# zehnder-comfoair-esp32.net
KiCad netlist of a schematic drawn in Altium Designer
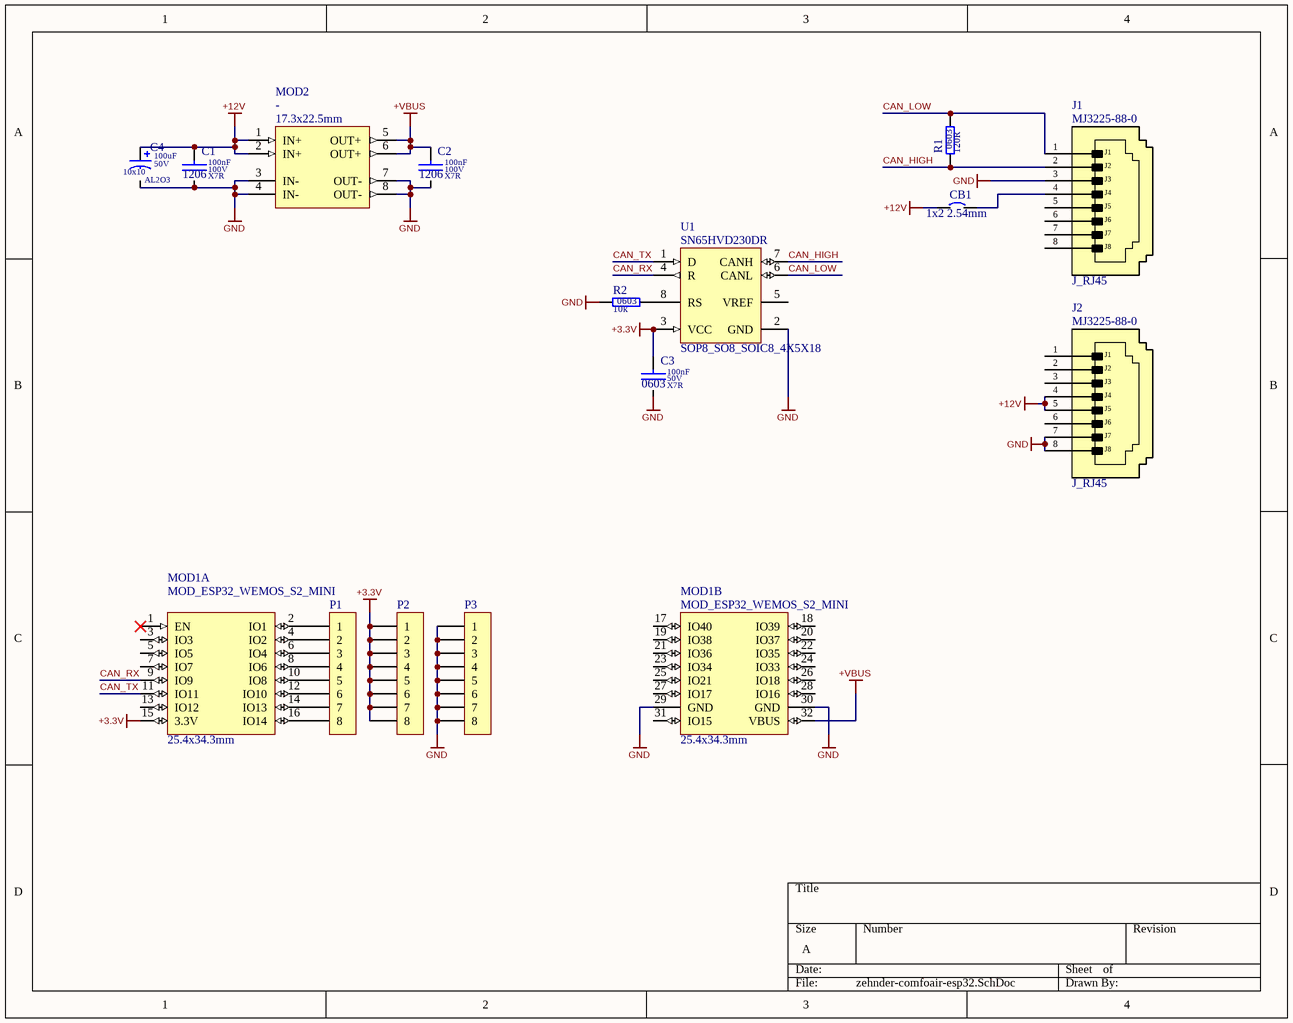
[diagram p0: zehnder-comfoair-esp32.SchDoc]

(export (version "E")
  (design (tool "Eeschema 10.0.6"))
  (components
    (comp (ref "C1")
      (value "100nF")
      (footprint "C_1206_3216")
      (description "Capacitor")
      (fields
        (field (name "DIELECTRIC") "X7R")
        (field (name "VOLTAGE") "100V")
        (field (name "SCH_FOOTPRINT") "1206")
        (field (name "PART NUMBER") "C_100nF_100V_X7R_1206_10")
        (field (name "MANUFACTURER") "Samsung")
      )
      (libsource (lib "Library") (part "C"))
    )
    (comp (ref "C2")
      (value "100nF")
      (footprint "C_1206_3216")
      (description "Capacitor")
      (fields
        (field (name "DIELECTRIC") "X7R")
        (field (name "VOLTAGE") "100V")
        (field (name "SCH_FOOTPRINT") "1206")
        (field (name "PART NUMBER") "C_100nF_100V_X7R_1206_10")
        (field (name "MANUFACTURER") "Samsung")
      )
      (libsource (lib "Library") (part "C"))
    )
    (comp (ref "C3")
      (value "100nF")
      (footprint "C_0603_1608")
      (description "Capacitor")
      (fields
        (field (name "DIELECTRIC") "X7R")
        (field (name "VOLTAGE") "50V")
        (field (name "SCH_FOOTPRINT") "0603")
        (field (name "PART NUMBER") "C_100nF_50V_X7R_0603_5")
        (field (name "MANUFACTURER") "Samsung")
      )
      (libsource (lib "Library") (part "C"))
    )
    (comp (ref "C4")
      (value "100uF")
      (footprint "CE_D_10x10MM")
      (description "Polarized Capacitor")
      (fields
        (field (name "DIELECTRIC") "AL2O3")
        (field (name "SCH_FOOTPRINT") "10x10")
        (field (name "VOLTAGE") "50V")
        (field (name "PART NUMBER") "CE_100uF_50V_AL2O3_10x10_20")
        (field (name "MANUFACTURER") "Nichicon")
      )
      (libsource (lib "Library") (part "CE"))
    )
    (comp (ref "CB1")
      (value "Goldpin")
      (footprint "P_HEADER_1x2_2.54")
      (description "Circuit Breaker")
      (fields (field (name "SCH_FOOTPRINT") "1x2 2.54mm") (field (name "PART NUMBER") "CB_GOLDPIN"))
      (libsource (lib "Library") (part "CB_CIRCUITBREAKER"))
    )
    (comp (ref "J1")
      (value "MJ3225-88-0")
      (footprint "J_RJ45_MJ3225-88-0")
      (fields
        (field (name "SCH_FOOTPRINT") "J_RJ45")
        (field (name "PART NUMBER") "J_RJ45_MJ3225-88-0")
        (field (name "MANUFACTURER") "Global Connector Technology")
        (field (name "Comment") "Modular Connector, Modular Jack, 1 x 1 (Port), 8P8C, Cat3")
      )
      (libsource (lib "Library") (part "J_RJ45"))
    )
    (comp (ref "J2")
      (value "MJ3225-88-0")
      (footprint "J_RJ45_MJ3225-88-0")
      (fields
        (field (name "SCH_FOOTPRINT") "J_RJ45")
        (field (name "PART NUMBER") "J_RJ45_MJ3225-88-0")
        (field (name "MANUFACTURER") "Global Connector Technology")
        (field (name "Comment") "Modular Connector, Modular Jack, 1 x 1 (Port), 8P8C, Cat3")
      )
      (libsource (lib "Library") (part "J_RJ45"))
    )
    (comp (ref "MOD1")
      (value "MOD_ESP32_WEMOS_S2_MINI")
      (footprint "MOD_ESP32_WEMOS_S2_MINI")
      (fields
        (field (name "SCH_FOOTPRINT") "25.4x34.3mm")
        (field (name "MANUFACTURER") "Wemos")
        (field (name "Comment") "ESP32-S2FN4R2 mini wifi board")
      )
      (libsource (lib "Library") (part "MOD_ESP32_WEMOS_S2_MINI"))
    )
    (comp (ref "MOD2")
      (value "-")
      (footprint "MOD_BUCK_MP1584")
      (fields
        (field (name "SCH_FOOTPRINT") "17.3x22.5mm")
        (field (name "PART NUMBER") "MOD_BUCK_MP1584")
        (field (name "Comment") "Low cost, Aliexpress-ready DC-DC buck converter using MP1584")
      )
      (libsource (lib "Library") (part "MOD_BUCK_MP1584"))
    )
    (comp (ref "P1")
      (value "Goldpin")
      (footprint "P_HEADER_1x8_2.54")
      (description "Pin Header")
      (fields (field (name "PART NUMBER") "P_HEADER_1x8_2.54") (field (name "MANUFACTURER") "Connfly"))
      (libsource (lib "Library") (part "P_HEADER_1x8"))
    )
    (comp (ref "P2")
      (value "Goldpin")
      (footprint "P_HEADER_1x8_2.54")
      (description "Pin Header")
      (fields (field (name "PART NUMBER") "P_HEADER_1x8_2.54") (field (name "MANUFACTURER") "Connfly"))
      (libsource (lib "Library") (part "P_HEADER_1x8"))
    )
    (comp (ref "P3")
      (value "Goldpin")
      (footprint "P_HEADER_1x8_2.54")
      (description "Pin Header")
      (fields (field (name "PART NUMBER") "P_HEADER_1x8_2.54") (field (name "MANUFACTURER") "Connfly"))
      (libsource (lib "Library") (part "P_HEADER_1x8"))
    )
    (comp (ref "R1")
      (value "120R")
      (footprint "R_0603_1608")
      (fields
        (field (name "SCH_FOOTPRINT") "0603")
        (field (name "PART NUMBER") "R_120R_0603_1")
        (field (name "VOLTAGE") "75V")
        (field (name "POWER") "100mW")
      )
      (libsource (lib "Library") (part "R"))
    )
    (comp (ref "R2")
      (value "10k")
      (footprint "R_0603_1608")
      (fields
        (field (name "SCH_FOOTPRINT") "0603")
        (field (name "PART NUMBER") "R_10k_0603_1")
        (field (name "VOLTAGE") "75V")
        (field (name "POWER") "100mW")
      )
      (libsource (lib "Library") (part "R"))
    )
    (comp (ref "U1")
      (value "SN65HVD230DR")
      (footprint "SOP8_SO8_SOIC8_4X5X18")
      (fields
        (field (name "SCH_FOOTPRINT") "SOP8_SO8_SOIC8_4X5X18")
        (field (name "PART NUMBER") "U_SN65HVD230DR")
        (field (name "MANUFACTURER") "Texas Instruments")
        (field (name "Comment") "SN65HVD23x 3.3-V CAN Bus Transceivers")
      )
      (libsource (lib "Library") (part "U_SN65HVD230"))
    )
  )
  (nets
    (net (code "1") (name "+3.3V") (class "Default")
      (node (ref "C3") (pin "1") (pinfunction "1_1") (pintype "passive"))
      (node (ref "MOD1") (pin "15") (pinfunction "3.3V_15") (pintype "bidirectional"))
      (node (ref "P2") (pin "1") (pinfunction "1_1") (pintype "passive"))
      (node (ref "P2") (pin "2") (pinfunction "2_2") (pintype "passive"))
      (node (ref "P2") (pin "3") (pinfunction "3_3") (pintype "passive"))
      (node (ref "P2") (pin "4") (pinfunction "4_4") (pintype "passive"))
      (node (ref "P2") (pin "5") (pinfunction "5_5") (pintype "passive"))
      (node (ref "P2") (pin "6") (pinfunction "6_6") (pintype "passive"))
      (node (ref "P2") (pin "7") (pinfunction "7_7") (pintype "passive"))
      (node (ref "P2") (pin "8") (pinfunction "8_8") (pintype "passive"))
      (node (ref "U1") (pin "3") (pinfunction "VCC_3") (pintype "input"))
    )
    (net (code "2") (name "+12V") (class "Default")
      (node (ref "C1") (pin "1") (pinfunction "1_1") (pintype "passive"))
      (node (ref "C4") (pin "1") (pinfunction "1_1") (pintype "passive"))
      (node (ref "CB1") (pin "1") (pinfunction "1_1") (pintype "passive"))
      (node (ref "J2") (pin "4") (pintype "passive"))
      (node (ref "J2") (pin "5") (pintype "passive"))
      (node (ref "MOD2") (pin "1") (pinfunction "IN+_1") (pintype "input"))
      (node (ref "MOD2") (pin "2") (pinfunction "IN+_2") (pintype "input"))
    )
    (net (code "3") (name "+VBUS") (class "Default")
      (node (ref "C2") (pin "1") (pinfunction "1_1") (pintype "passive"))
      (node (ref "MOD1") (pin "32") (pinfunction "VBUS_32") (pintype "bidirectional"))
      (node (ref "MOD2") (pin "5") (pinfunction "OUT+_5") (pintype "output"))
      (node (ref "MOD2") (pin "6") (pinfunction "OUT+_6") (pintype "output"))
    )
    (net (code "4") (name "/CAN_HIGH") (class "Default")
      (node (ref "J1") (pin "2") (pintype "passive"))
      (node (ref "R1") (pin "1") (pinfunction "1_1") (pintype "passive"))
      (node (ref "U1") (pin "7") (pinfunction "CANH_7") (pintype "bidirectional"))
    )
    (net (code "5") (name "/CAN_LOW") (class "Default")
      (node (ref "J1") (pin "1") (pintype "passive"))
      (node (ref "R1") (pin "2") (pinfunction "2_2") (pintype "passive"))
      (node (ref "U1") (pin "6") (pinfunction "CANL_6") (pintype "bidirectional"))
    )
    (net (code "6") (name "/CAN_RX") (class "Default")
      (node (ref "MOD1") (pin "9") (pinfunction "IO9_9") (pintype "bidirectional"))
      (node (ref "U1") (pin "4") (pinfunction "R_4") (pintype "output"))
    )
    (net (code "7") (name "/CAN_TX") (class "Default")
      (node (ref "MOD1") (pin "11") (pinfunction "IO11_11") (pintype "bidirectional"))
      (node (ref "U1") (pin "1") (pinfunction "D_1") (pintype "input"))
    )
    (net (code "8") (name "GND") (class "Default")
      (node (ref "C1") (pin "2") (pinfunction "2_2") (pintype "passive"))
      (node (ref "C2") (pin "2") (pinfunction "2_2") (pintype "passive"))
      (node (ref "C3") (pin "2") (pinfunction "2_2") (pintype "passive"))
      (node (ref "C4") (pin "2") (pinfunction "2_2") (pintype "passive"))
      (node (ref "J1") (pin "3") (pintype "passive"))
      (node (ref "J2") (pin "7") (pintype "passive"))
      (node (ref "J2") (pin "8") (pintype "passive"))
      (node (ref "MOD1") (pin "29") (pinfunction "GND_29") (pintype "power_in"))
      (node (ref "MOD1") (pin "30") (pinfunction "GND_30") (pintype "power_in"))
      (node (ref "MOD2") (pin "3") (pinfunction "IN-_3") (pintype "power_in"))
      (node (ref "MOD2") (pin "4") (pinfunction "IN-_4") (pintype "power_in"))
      (node (ref "MOD2") (pin "7") (pinfunction "OUT-_7") (pintype "output"))
      (node (ref "MOD2") (pin "8") (pinfunction "OUT-_8") (pintype "output"))
      (node (ref "P3") (pin "1") (pinfunction "1_1") (pintype "passive"))
      (node (ref "P3") (pin "2") (pinfunction "2_2") (pintype "passive"))
      (node (ref "P3") (pin "3") (pinfunction "3_3") (pintype "passive"))
      (node (ref "P3") (pin "4") (pinfunction "4_4") (pintype "passive"))
      (node (ref "P3") (pin "5") (pinfunction "5_5") (pintype "passive"))
      (node (ref "P3") (pin "6") (pinfunction "6_6") (pintype "passive"))
      (node (ref "P3") (pin "7") (pinfunction "7_7") (pintype "passive"))
      (node (ref "P3") (pin "8") (pinfunction "8_8") (pintype "passive"))
      (node (ref "R2") (pin "1") (pinfunction "1_1") (pintype "passive"))
      (node (ref "U1") (pin "2") (pinfunction "GND_2") (pintype "power_in"))
    )
    (net (code "9") (name "Net-(CB1-Pad2)") (class "Default")
      (node (ref "CB1") (pin "2") (pinfunction "2_2") (pintype "passive"))
      (node (ref "J1") (pin "4") (pintype "passive"))
    )
    (net (code "10") (name "Net-(MOD1A-IO1)") (class "Default")
      (node (ref "MOD1") (pin "2") (pinfunction "IO1_2") (pintype "bidirectional"))
      (node (ref "P1") (pin "1") (pinfunction "1_1") (pintype "passive"))
    )
    (net (code "11") (name "Net-(MOD1A-IO2)") (class "Default")
      (node (ref "MOD1") (pin "4") (pinfunction "IO2_4") (pintype "bidirectional"))
      (node (ref "P1") (pin "2") (pinfunction "2_2") (pintype "passive"))
    )
    (net (code "12") (name "Net-(MOD1A-IO4)") (class "Default")
      (node (ref "MOD1") (pin "6") (pinfunction "IO4_6") (pintype "bidirectional"))
      (node (ref "P1") (pin "3") (pinfunction "3_3") (pintype "passive"))
    )
    (net (code "13") (name "Net-(MOD1A-IO6)") (class "Default")
      (node (ref "MOD1") (pin "8") (pinfunction "IO6_8") (pintype "bidirectional"))
      (node (ref "P1") (pin "4") (pinfunction "4_4") (pintype "passive"))
    )
    (net (code "14") (name "Net-(MOD1A-IO8)") (class "Default")
      (node (ref "MOD1") (pin "10") (pinfunction "IO8_10") (pintype "bidirectional"))
      (node (ref "P1") (pin "5") (pinfunction "5_5") (pintype "passive"))
    )
    (net (code "15") (name "Net-(MOD1A-IO10)") (class "Default")
      (node (ref "MOD1") (pin "12") (pinfunction "IO10_12") (pintype "bidirectional"))
      (node (ref "P1") (pin "6") (pinfunction "6_6") (pintype "passive"))
    )
    (net (code "16") (name "Net-(MOD1A-IO13)") (class "Default")
      (node (ref "MOD1") (pin "14") (pinfunction "IO13_14") (pintype "bidirectional"))
      (node (ref "P1") (pin "7") (pinfunction "7_7") (pintype "passive"))
    )
    (net (code "17") (name "Net-(MOD1A-IO14)") (class "Default")
      (node (ref "MOD1") (pin "16") (pinfunction "IO14_16") (pintype "bidirectional"))
      (node (ref "P1") (pin "8") (pinfunction "8_8") (pintype "passive"))
    )
    (net (code "18") (name "Net-(U1-RS)") (class "Default")
      (node (ref "R2") (pin "2") (pinfunction "2_2") (pintype "passive"))
      (node (ref "U1") (pin "8") (pinfunction "RS_8") (pintype "passive"))
    )
    (net (code "19") (name "unconnected-(J1-Pad5)") (class "Default")
      (node (ref "J1") (pin "5") (pintype "passive"))
    )
    (net (code "20") (name "unconnected-(J1-Pad6)") (class "Default")
      (node (ref "J1") (pin "6") (pintype "passive"))
    )
    (net (code "21") (name "unconnected-(J1-Pad7)") (class "Default")
      (node (ref "J1") (pin "7") (pintype "passive"))
    )
    (net (code "22") (name "unconnected-(J1-Pad8)") (class "Default")
      (node (ref "J1") (pin "8") (pintype "passive"))
    )
    (net (code "23") (name "unconnected-(J2-Pad1)") (class "Default")
      (node (ref "J2") (pin "1") (pintype "passive"))
    )
    (net (code "24") (name "unconnected-(J2-Pad2)") (class "Default")
      (node (ref "J2") (pin "2") (pintype "passive"))
    )
    (net (code "25") (name "unconnected-(J2-Pad3)") (class "Default")
      (node (ref "J2") (pin "3") (pintype "passive"))
    )
    (net (code "26") (name "unconnected-(J2-Pad6)") (class "Default")
      (node (ref "J2") (pin "6") (pintype "passive"))
    )
    (net (code "27") (name "unconnected-(MOD1A-EN-Pad1)") (class "Default")
      (node (ref "MOD1") (pin "1") (pinfunction "EN_1") (pintype "input+no_connect"))
    )
    (net (code "28") (name "unconnected-(MOD1A-IO3-Pad3)") (class "Default")
      (node (ref "MOD1") (pin "3") (pinfunction "IO3_3") (pintype "bidirectional"))
    )
    (net (code "29") (name "unconnected-(MOD1A-IO5-Pad5)") (class "Default")
      (node (ref "MOD1") (pin "5") (pinfunction "IO5_5") (pintype "bidirectional"))
    )
    (net (code "30") (name "unconnected-(MOD1A-IO7-Pad7)") (class "Default")
      (node (ref "MOD1") (pin "7") (pinfunction "IO7_7") (pintype "bidirectional"))
    )
    (net (code "31") (name "unconnected-(MOD1A-IO12-Pad13)") (class "Default")
      (node (ref "MOD1") (pin "13") (pinfunction "IO12_13") (pintype "bidirectional"))
    )
    (net (code "32") (name "unconnected-(MOD1B-IO15-Pad31)") (class "Default")
      (node (ref "MOD1") (pin "31") (pinfunction "IO15_31") (pintype "bidirectional"))
    )
    (net (code "33") (name "unconnected-(MOD1B-IO16-Pad28)") (class "Default")
      (node (ref "MOD1") (pin "28") (pinfunction "IO16_28") (pintype "bidirectional"))
    )
    (net (code "34") (name "unconnected-(MOD1B-IO17-Pad27)") (class "Default")
      (node (ref "MOD1") (pin "27") (pinfunction "IO17_27") (pintype "bidirectional"))
    )
    (net (code "35") (name "unconnected-(MOD1B-IO18-Pad26)") (class "Default")
      (node (ref "MOD1") (pin "26") (pinfunction "IO18_26") (pintype "bidirectional"))
    )
    (net (code "36") (name "unconnected-(MOD1B-IO21-Pad25)") (class "Default")
      (node (ref "MOD1") (pin "25") (pinfunction "IO21_25") (pintype "bidirectional"))
    )
    (net (code "37") (name "unconnected-(MOD1B-IO33-Pad24)") (class "Default")
      (node (ref "MOD1") (pin "24") (pinfunction "IO33_24") (pintype "bidirectional"))
    )
    (net (code "38") (name "unconnected-(MOD1B-IO34-Pad23)") (class "Default")
      (node (ref "MOD1") (pin "23") (pinfunction "IO34_23") (pintype "bidirectional"))
    )
    (net (code "39") (name "unconnected-(MOD1B-IO35-Pad22)") (class "Default")
      (node (ref "MOD1") (pin "22") (pinfunction "IO35_22") (pintype "bidirectional"))
    )
    (net (code "40") (name "unconnected-(MOD1B-IO36-Pad21)") (class "Default")
      (node (ref "MOD1") (pin "21") (pinfunction "IO36_21") (pintype "bidirectional"))
    )
    (net (code "41") (name "unconnected-(MOD1B-IO37-Pad20)") (class "Default")
      (node (ref "MOD1") (pin "20") (pinfunction "IO37_20") (pintype "bidirectional"))
    )
    (net (code "42") (name "unconnected-(MOD1B-IO38-Pad19)") (class "Default")
      (node (ref "MOD1") (pin "19") (pinfunction "IO38_19") (pintype "bidirectional"))
    )
    (net (code "43") (name "unconnected-(MOD1B-IO39-Pad18)") (class "Default")
      (node (ref "MOD1") (pin "18") (pinfunction "IO39_18") (pintype "bidirectional"))
    )
    (net (code "44") (name "unconnected-(MOD1B-IO40-Pad17)") (class "Default")
      (node (ref "MOD1") (pin "17") (pinfunction "IO40_17") (pintype "bidirectional"))
    )
    (net (code "45") (name "unconnected-(U1-VREF-Pad5)") (class "Default")
      (node (ref "U1") (pin "5") (pinfunction "VREF_5") (pintype "passive"))
    )
  )
)
